# Lab3.net
KiCad netlist of a schematic drawn in EAGLE
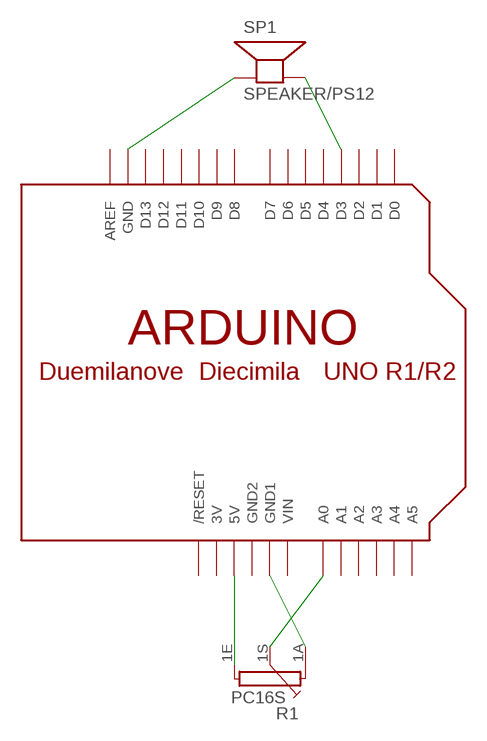
[diagram p0: schematic, sheet 1]

(export (version "E")
  (design (tool "Eeschema 10.0.6"))
  (components
    (comp (ref "R1")
      (value "PC16S")
      (footprint "eagle-import:PC16S")
      (libsource (lib "eagle-import") (part "PC16S"))
    )
    (comp (ref "SP1")
      (value "SPEAKER/PS12")
      (footprint "eagle-import:PS12")
      (libsource (lib "eagle-import") (part "SPEAKER/PS12"))
    )
    (comp (ref "U$1")
      (value "ARDUINO-BPLACE")
      (footprint "eagle-import:ARDUINO-BPLACE")
      (libsource (lib "eagle-import") (part "ARDUINO-BPLACE"))
    )
  )
  (nets
    (net (code "1") (name "/3V") (class "Default")
      (node (ref "U$1") (pin "3V") (pinfunction "3V_3V") (pintype "power_in"))
    )
    (net (code "2") (name "/GND2") (class "Default")
      (node (ref "U$1") (pin "GND2") (pinfunction "GND2_GND2") (pintype "power_in"))
    )
    (net (code "3") (name "/VIN") (class "Default")
      (node (ref "U$1") (pin "VIN") (pinfunction "VIN_VIN") (pintype "power_in"))
    )
    (net (code "4") (name "Net-(R1-Pad1A)") (class "Default")
      (node (ref "R1") (pin "1A") (pinfunction "1A_1A") (pintype "passive"))
      (node (ref "U$1") (pin "GND1") (pinfunction "GND1_GND1") (pintype "power_in"))
    )
    (net (code "5") (name "Net-(R1-Pad1S)") (class "Default")
      (node (ref "R1") (pin "1S") (pinfunction "1S_1S") (pintype "passive"))
      (node (ref "U$1") (pin "A0") (pinfunction "A0_A0") (pintype "bidirectional"))
    )
    (net (code "6") (name "Net-(SP1-+)") (class "Default")
      (node (ref "SP1") (pin "P$1") (pinfunction "+_P$1") (pintype "passive"))
      (node (ref "U$1") (pin "GND") (pinfunction "GND_GND") (pintype "power_in"))
    )
    (net (code "7") (name "Net-(SP1--)") (class "Default")
      (node (ref "SP1") (pin "P$2") (pinfunction "-_P$2") (pintype "passive"))
      (node (ref "U$1") (pin "D3") (pinfunction "D3_D3") (pintype "bidirectional"))
    )
    (net (code "8") (name "unconnected-(R1-Pad1E)") (class "Default")
      (node (ref "R1") (pin "1E") (pinfunction "1E_1E") (pintype "passive"))
    )
    (net (code "9") (name "unconnected-(U$1-Pad5V)") (class "Default")
      (node (ref "U$1") (pin "5V") (pinfunction "5V_5V") (pintype "power_in"))
    )
    (net (code "10") (name "unconnected-(U$1-PadA1)") (class "Default")
      (node (ref "U$1") (pin "A1") (pinfunction "A1_A1") (pintype "bidirectional"))
    )
    (net (code "11") (name "unconnected-(U$1-PadA2)") (class "Default")
      (node (ref "U$1") (pin "A2") (pinfunction "A2_A2") (pintype "bidirectional"))
    )
    (net (code "12") (name "unconnected-(U$1-PadA3)") (class "Default")
      (node (ref "U$1") (pin "A3") (pinfunction "A3_A3") (pintype "bidirectional"))
    )
    (net (code "13") (name "unconnected-(U$1-PadA4)") (class "Default")
      (node (ref "U$1") (pin "A4") (pinfunction "A4_A4") (pintype "bidirectional"))
    )
    (net (code "14") (name "unconnected-(U$1-PadA5)") (class "Default")
      (node (ref "U$1") (pin "A5") (pinfunction "A5_A5") (pintype "bidirectional"))
    )
    (net (code "15") (name "unconnected-(U$1-PadAREF)") (class "Default")
      (node (ref "U$1") (pin "AREF") (pinfunction "AREF_AREF") (pintype "bidirectional"))
    )
    (net (code "16") (name "unconnected-(U$1-PadD0)") (class "Default")
      (node (ref "U$1") (pin "D0") (pinfunction "D0_D0") (pintype "bidirectional"))
    )
    (net (code "17") (name "unconnected-(U$1-PadD1)") (class "Default")
      (node (ref "U$1") (pin "D1") (pinfunction "D1_D1") (pintype "bidirectional"))
    )
    (net (code "18") (name "unconnected-(U$1-PadD2)") (class "Default")
      (node (ref "U$1") (pin "D2") (pinfunction "D2_D2") (pintype "bidirectional"))
    )
    (net (code "19") (name "unconnected-(U$1-PadD4)") (class "Default")
      (node (ref "U$1") (pin "D4") (pinfunction "D4_D4") (pintype "bidirectional"))
    )
    (net (code "20") (name "unconnected-(U$1-PadD5)") (class "Default")
      (node (ref "U$1") (pin "D5") (pinfunction "D5_D5") (pintype "bidirectional"))
    )
    (net (code "21") (name "unconnected-(U$1-PadD6)") (class "Default")
      (node (ref "U$1") (pin "D6") (pinfunction "D6_D6") (pintype "bidirectional"))
    )
    (net (code "22") (name "unconnected-(U$1-PadD7)") (class "Default")
      (node (ref "U$1") (pin "D7") (pinfunction "D7_D7") (pintype "bidirectional"))
    )
    (net (code "23") (name "unconnected-(U$1-PadD8)") (class "Default")
      (node (ref "U$1") (pin "D8") (pinfunction "D8_D8") (pintype "bidirectional"))
    )
    (net (code "24") (name "unconnected-(U$1-PadD9)") (class "Default")
      (node (ref "U$1") (pin "D9") (pinfunction "D9_D9") (pintype "bidirectional"))
    )
    (net (code "25") (name "unconnected-(U$1-PadD10)") (class "Default")
      (node (ref "U$1") (pin "D10") (pinfunction "D10_D10") (pintype "bidirectional"))
    )
    (net (code "26") (name "unconnected-(U$1-PadD11)") (class "Default")
      (node (ref "U$1") (pin "D11") (pinfunction "D11_D11") (pintype "bidirectional"))
    )
    (net (code "27") (name "unconnected-(U$1-PadD12)") (class "Default")
      (node (ref "U$1") (pin "D12") (pinfunction "D12_D12") (pintype "bidirectional"))
    )
    (net (code "28") (name "unconnected-(U$1-PadD13)") (class "Default")
      (node (ref "U$1") (pin "D13") (pinfunction "D13_D13") (pintype "bidirectional"))
    )
    (net (code "29") (name "unconnected-(U$1-{slash}RESET-PadRESET)") (class "Default")
      (node (ref "U$1") (pin "RESET") (pinfunction "/RESET_RESET") (pintype "bidirectional"))
    )
  )
)
